# Schematics-IO.net
KiCad netlist of a schematic drawn in Altium Designer
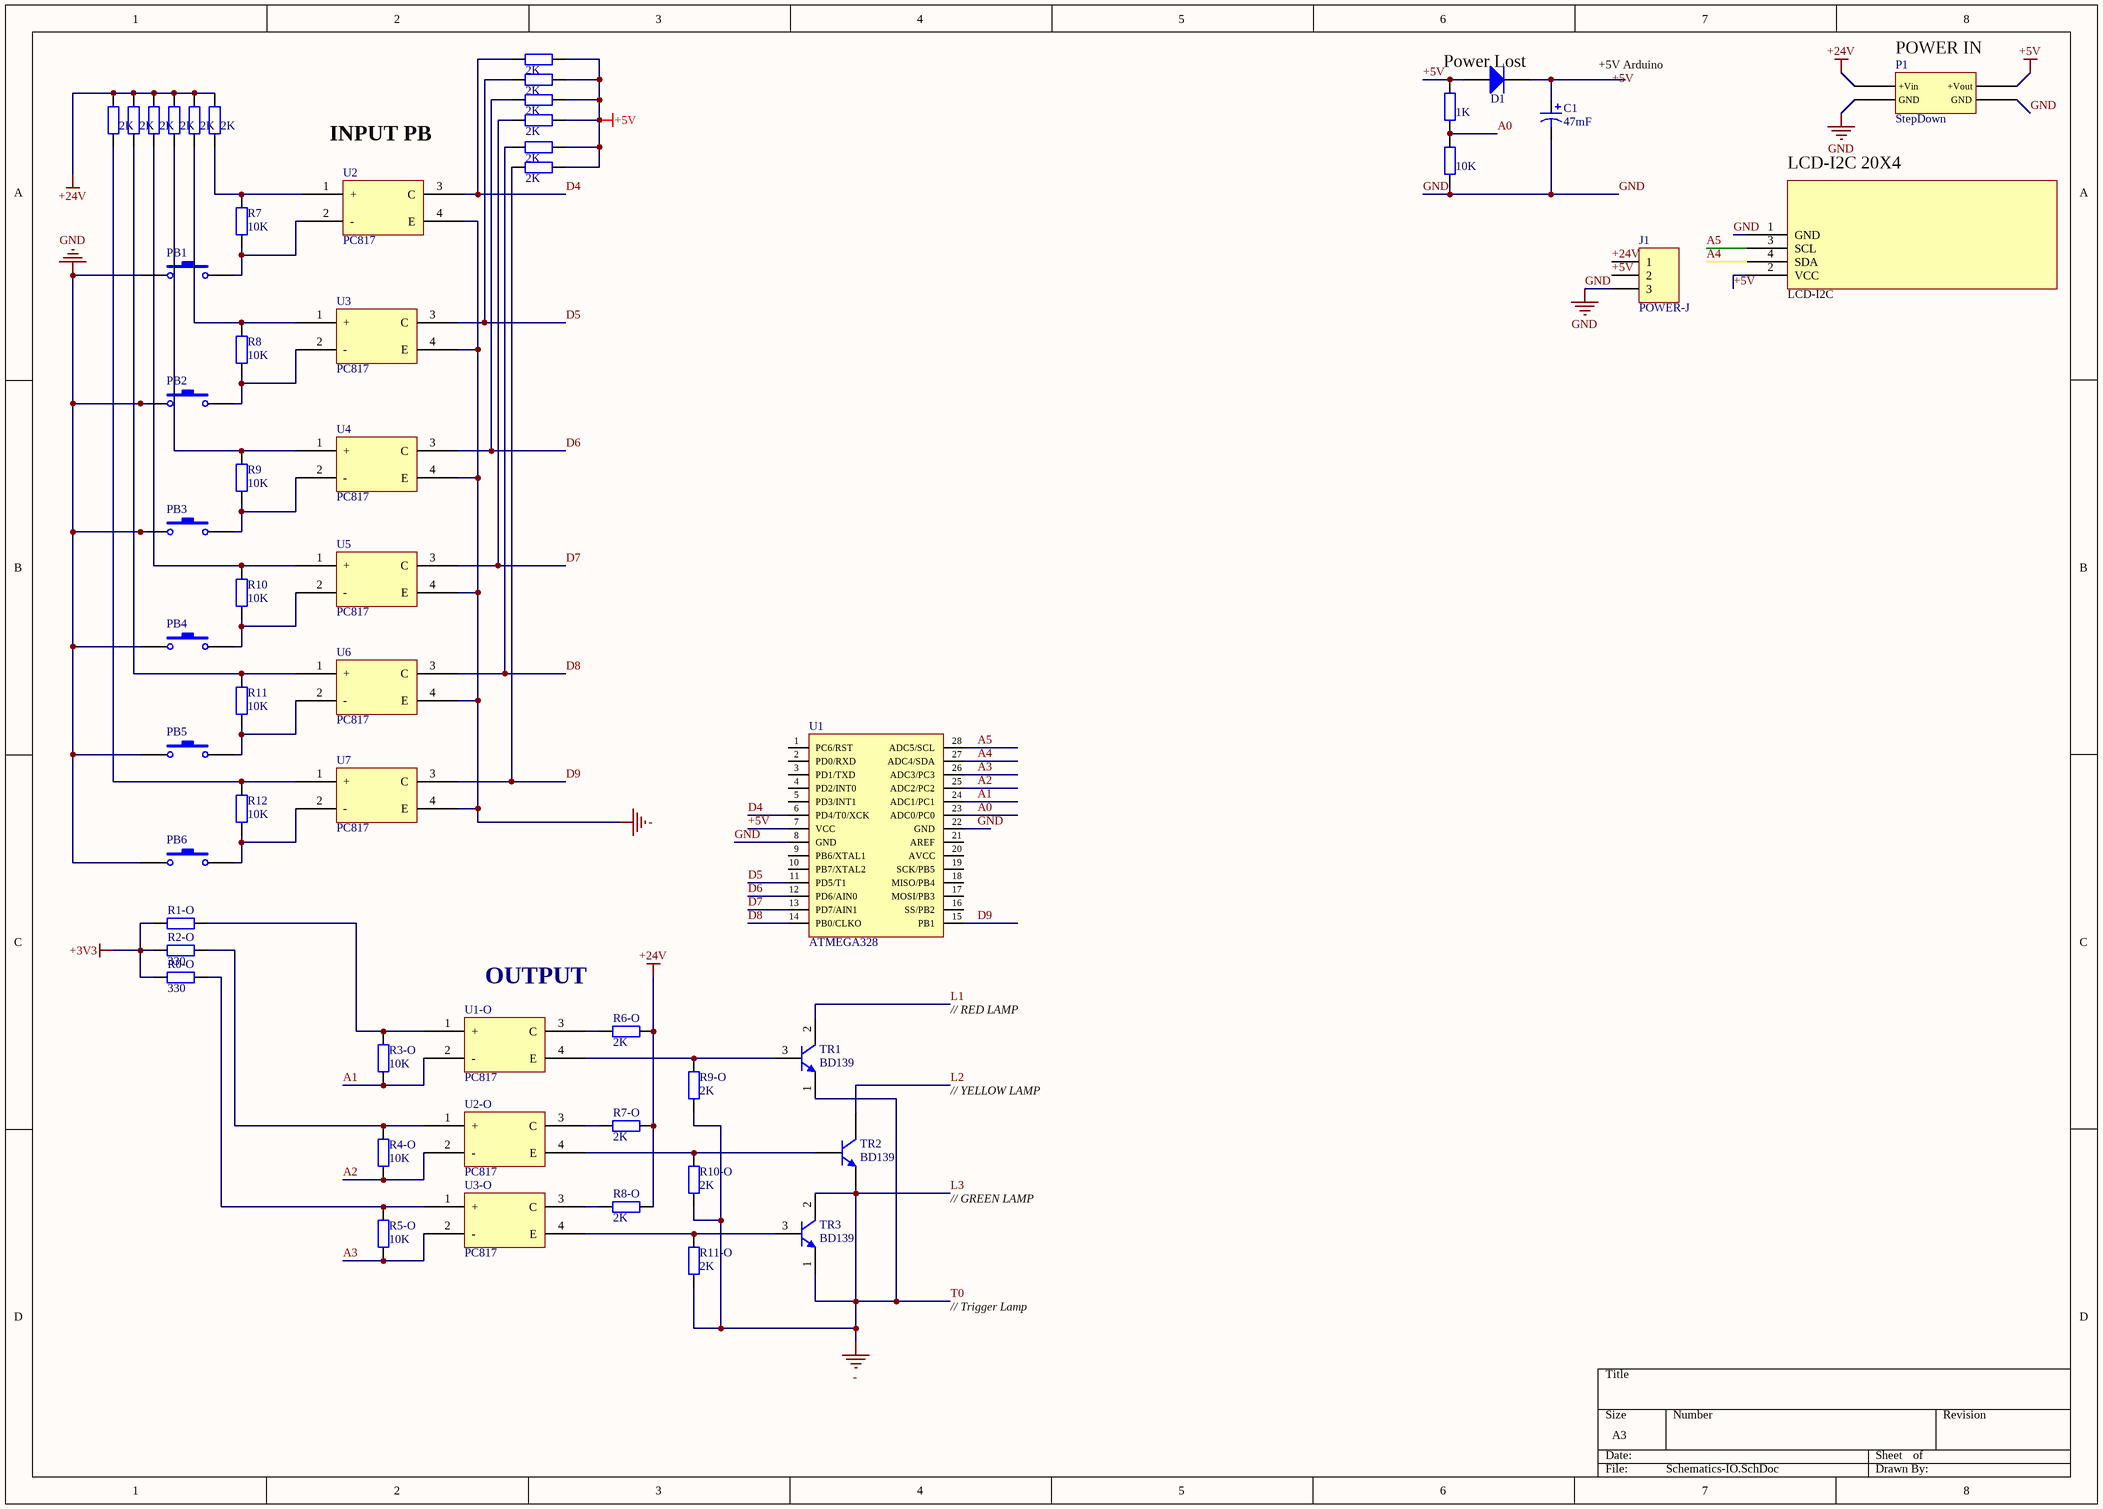
[diagram p0: Schematics-IO.SchDoc]

(export (version "E")
  (design (tool "Eeschema 10.0.6"))
  (components
    (comp (ref "C1")
      (value "47mF")
      (footprint "RB7.6-15")
      (description "Polarized Capacitor (Radial)")
      (fields (field (name "Comment") "p Pol1") (field (name "PUBLISHER") "Altium Limited"))
      (libsource (lib "Miscellaneous Devices") (part "Cap Pol1"))
    )
    (comp (ref "D1")
      (value "Diode")
      (footprint "SMC")
      (description "Default Diode")
      (fields (field (name "PUBLISHER") "Altium Limited"))
      (libsource (lib "Miscellaneous Devices") (part "Diode"))
    )
    (comp (ref "J1")
      (value "POWER-J")
      (footprint "HDR1X3")
      (description "Header, 3-Pin")
      (fields (field (name "PUBLISHER") "Altium Limited"))
      (libsource (lib "Miscellaneous Connectors") (part "Header 3"))
    )
    (comp (ref "P1") (value "StepDown") (footprint "MODULE4") (libsource (lib "LIBRARY_1") (part "StepDown")))
    (comp (ref "PB1")
      (value "NG+")
      (footprint "SPST-2")
      (description "Switch")
      (fields (field (name "PUBLISHER") "Altium Limited"))
      (libsource (lib "Miscellaneous Devices") (part "SW-PB"))
    )
    (comp (ref "PB2")
      (value "NG+")
      (footprint "SPST-2")
      (description "Switch")
      (fields (field (name "PUBLISHER") "Altium Limited"))
      (libsource (lib "Miscellaneous Devices") (part "SW-PB"))
    )
    (comp (ref "PB3")
      (value "NG+")
      (footprint "SPST-2")
      (description "Switch")
      (fields (field (name "PUBLISHER") "Altium Limited"))
      (libsource (lib "Miscellaneous Devices") (part "SW-PB"))
    )
    (comp (ref "PB4")
      (value "NG+")
      (footprint "SPST-2")
      (description "Switch")
      (fields (field (name "PUBLISHER") "Altium Limited"))
      (libsource (lib "Miscellaneous Devices") (part "SW-PB"))
    )
    (comp (ref "PB5")
      (value "NG+")
      (footprint "SPST-2")
      (description "Switch")
      (fields (field (name "PUBLISHER") "Altium Limited"))
      (libsource (lib "Miscellaneous Devices") (part "SW-PB"))
    )
    (comp (ref "PB6")
      (value "NG+")
      (footprint "SPST-2")
      (description "Switch")
      (fields (field (name "PUBLISHER") "Altium Limited"))
      (libsource (lib "Miscellaneous Devices") (part "SW-PB"))
    )
    (comp (ref "R0-O")
      (value "330")
      (footprint "AXIAL-0.4")
      (description "Resistor")
      (fields (field (name "Comment") "Res2") (field (name "PUBLISHER") "Altium Limited"))
      (libsource (lib "Miscellaneous Devices") (part "Res2"))
    )
    (comp (ref "R1")
      (value "2K")
      (footprint "AXIAL-0.4")
      (description "Resistor")
      (fields (field (name "Comment") "Res2") (field (name "PUBLISHER") "Altium Limited"))
      (libsource (lib "") (part "Res2_1"))
    )
    (comp (ref "R1-O")
      (value "Res2")
      (footprint "AXIAL-0.4")
      (description "Resistor")
      (fields (field (name "PUBLISHER") "Altium Limited"))
      (libsource (lib "Miscellaneous Devices") (part "Res2"))
    )
    (comp (ref "R2")
      (value "2K")
      (footprint "AXIAL-0.4")
      (description "Resistor")
      (fields (field (name "Comment") "Res2") (field (name "PUBLISHER") "Altium Limited"))
      (libsource (lib "") (part "Res2_1"))
    )
    (comp (ref "R2-O")
      (value "330")
      (footprint "AXIAL-0.4")
      (description "Resistor")
      (fields (field (name "Comment") "Res2") (field (name "PUBLISHER") "Altium Limited"))
      (libsource (lib "Miscellaneous Devices") (part "Res2"))
    )
    (comp (ref "R3")
      (value "2K")
      (footprint "AXIAL-0.4")
      (description "Resistor")
      (fields (field (name "Comment") "Res2") (field (name "PUBLISHER") "Altium Limited"))
      (libsource (lib "") (part "Res2_1"))
    )
    (comp (ref "R3-O")
      (value "10K")
      (footprint "AXIAL-0.4")
      (description "Resistor")
      (fields (field (name "Comment") "Res2") (field (name "PUBLISHER") "Altium Limited"))
      (libsource (lib "") (part "Res2_1"))
    )
    (comp (ref "R4")
      (value "2K")
      (footprint "AXIAL-0.4")
      (description "Resistor")
      (fields (field (name "Comment") "Res2") (field (name "PUBLISHER") "Altium Limited"))
      (libsource (lib "") (part "Res2_1"))
    )
    (comp (ref "R4-O")
      (value "10K")
      (footprint "AXIAL-0.4")
      (description "Resistor")
      (fields (field (name "Comment") "Res2") (field (name "PUBLISHER") "Altium Limited"))
      (libsource (lib "") (part "Res2_1"))
    )
    (comp (ref "R5")
      (value "2K")
      (footprint "AXIAL-0.4")
      (description "Resistor")
      (fields (field (name "Comment") "Res2") (field (name "PUBLISHER") "Altium Limited"))
      (libsource (lib "") (part "Res2_1"))
    )
    (comp (ref "R5-O")
      (value "10K")
      (footprint "AXIAL-0.4")
      (description "Resistor")
      (fields (field (name "Comment") "Res2") (field (name "PUBLISHER") "Altium Limited"))
      (libsource (lib "") (part "Res2_1"))
    )
    (comp (ref "R6")
      (value "2K")
      (footprint "AXIAL-0.4")
      (description "Resistor")
      (fields (field (name "Comment") "Res2") (field (name "PUBLISHER") "Altium Limited"))
      (libsource (lib "") (part "Res2_1"))
    )
    (comp (ref "R6-O")
      (value "2K")
      (footprint "AXIAL-0.4")
      (description "Resistor")
      (fields (field (name "Comment") "Res2") (field (name "PUBLISHER") "Altium Limited"))
      (libsource (lib "Miscellaneous Devices") (part "Res2"))
    )
    (comp (ref "R7")
      (value "10K")
      (footprint "AXIAL-0.4")
      (description "Resistor")
      (fields (field (name "Comment") "Res2") (field (name "PUBLISHER") "Altium Limited"))
      (libsource (lib "") (part "Res2_3"))
    )
    (comp (ref "R7-O")
      (value "2K")
      (footprint "AXIAL-0.4")
      (description "Resistor")
      (fields (field (name "Comment") "Res2") (field (name "PUBLISHER") "Altium Limited"))
      (libsource (lib "Miscellaneous Devices") (part "Res2"))
    )
    (comp (ref "R8")
      (value "10K")
      (footprint "AXIAL-0.4")
      (description "Resistor")
      (fields (field (name "Comment") "Res2") (field (name "PUBLISHER") "Altium Limited"))
      (libsource (lib "") (part "Res2_3"))
    )
    (comp (ref "R8-O")
      (value "2K")
      (footprint "AXIAL-0.4")
      (description "Resistor")
      (fields (field (name "Comment") "Res2") (field (name "PUBLISHER") "Altium Limited"))
      (libsource (lib "Miscellaneous Devices") (part "Res2"))
    )
    (comp (ref "R9")
      (value "10K")
      (footprint "AXIAL-0.4")
      (description "Resistor")
      (fields (field (name "Comment") "Res2") (field (name "PUBLISHER") "Altium Limited"))
      (libsource (lib "") (part "Res2_3"))
    )
    (comp (ref "R9-O")
      (value "2K")
      (footprint "AXIAL-0.4")
      (description "Resistor")
      (fields (field (name "Comment") "Res2") (field (name "PUBLISHER") "Altium Limited"))
      (libsource (lib "") (part "Res2_3"))
    )
    (comp (ref "R10")
      (value "10K")
      (footprint "AXIAL-0.4")
      (description "Resistor")
      (fields (field (name "Comment") "Res2") (field (name "PUBLISHER") "Altium Limited"))
      (libsource (lib "") (part "Res2_3"))
    )
    (comp (ref "R10-O")
      (value "2K")
      (footprint "AXIAL-0.4")
      (description "Resistor")
      (fields (field (name "Comment") "Res2") (field (name "PUBLISHER") "Altium Limited"))
      (libsource (lib "") (part "Res2_3"))
    )
    (comp (ref "R11")
      (value "10K")
      (footprint "AXIAL-0.4")
      (description "Resistor")
      (fields (field (name "Comment") "Res2") (field (name "PUBLISHER") "Altium Limited"))
      (libsource (lib "") (part "Res2_3"))
    )
    (comp (ref "R11-O")
      (value "2K")
      (footprint "AXIAL-0.4")
      (description "Resistor")
      (fields (field (name "Comment") "Res2") (field (name "PUBLISHER") "Altium Limited"))
      (libsource (lib "") (part "Res2_3"))
    )
    (comp (ref "R12")
      (value "10K")
      (footprint "AXIAL-0.4")
      (description "Resistor")
      (fields (field (name "Comment") "Res2") (field (name "PUBLISHER") "Altium Limited"))
      (libsource (lib "") (part "Res2_3"))
    )
    (comp (ref "R13")
      (value "2K")
      (footprint "AXIAL-0.4")
      (description "Resistor")
      (fields (field (name "Comment") "Res2") (field (name "PUBLISHER") "Altium Limited"))
      (libsource (lib "") (part "Res2_2"))
    )
    (comp (ref "R14")
      (value "2K")
      (footprint "AXIAL-0.4")
      (description "Resistor")
      (fields (field (name "Comment") "Res2") (field (name "PUBLISHER") "Altium Limited"))
      (libsource (lib "") (part "Res2_2"))
    )
    (comp (ref "R15")
      (value "2K")
      (footprint "AXIAL-0.4")
      (description "Resistor")
      (fields (field (name "Comment") "Res2") (field (name "PUBLISHER") "Altium Limited"))
      (libsource (lib "") (part "Res2_2"))
    )
    (comp (ref "R16")
      (value "2K")
      (footprint "AXIAL-0.4")
      (description "Resistor")
      (fields (field (name "Comment") "Res2") (field (name "PUBLISHER") "Altium Limited"))
      (libsource (lib "") (part "Res2_2"))
    )
    (comp (ref "R17")
      (value "2K")
      (footprint "AXIAL-0.4")
      (description "Resistor")
      (fields (field (name "Comment") "Res2") (field (name "PUBLISHER") "Altium Limited"))
      (libsource (lib "") (part "Res2_2"))
    )
    (comp (ref "R18")
      (value "2K")
      (footprint "AXIAL-0.4")
      (description "Resistor")
      (fields (field (name "Comment") "Res2") (field (name "PUBLISHER") "Altium Limited"))
      (libsource (lib "") (part "Res2_2"))
    )
    (comp (ref "R19")
      (value "1K")
      (footprint "AXIAL-0.4")
      (description "Resistor")
      (fields (field (name "Comment") "Res2") (field (name "PUBLISHER") "Altium Limited"))
      (libsource (lib "") (part "Res2_1"))
    )
    (comp (ref "R20")
      (value "10K")
      (footprint "AXIAL-0.4")
      (description "Resistor")
      (fields (field (name "Comment") "Res2") (field (name "PUBLISHER") "Altium Limited"))
      (libsource (lib "") (part "Res2_1"))
    )
    (comp (ref "TR1")
      (value "BD139")
      (footprint "BD139")
      (description "NPN General Purpose Amplifier")
      (fields (field (name "PUBLISHER") "Altium Limited"))
      (libsource (lib "Miscellaneous Devices") (part "2N3904"))
    )
    (comp (ref "TR2")
      (value "BD139")
      (footprint "BD139")
      (description "NPN General Purpose Amplifier")
      (fields (field (name "PUBLISHER") "Altium Limited"))
      (libsource (lib "") (part "2N3904_1"))
    )
    (comp (ref "TR3")
      (value "BD139")
      (footprint "BD139")
      (description "NPN General Purpose Amplifier")
      (fields (field (name "PUBLISHER") "Altium Limited"))
      (libsource (lib "Miscellaneous Devices") (part "2N3904"))
    )
    (comp (ref "U1") (value "ATMEGA328") (footprint "at328") (libsource (lib "LIBRARY_1") (part "ATMEGA328")))
    (comp (ref "U1-O") (value "PC817") (footprint "PC817") (libsource (lib "LIBRARY_1") (part "PC817")))
    (comp (ref "U2") (value "PC817") (footprint "PC817") (libsource (lib "LIBRARY_1") (part "PC817")))
    (comp (ref "U2-O") (value "PC817") (footprint "PC817") (libsource (lib "LIBRARY_1") (part "PC817")))
    (comp (ref "U3") (value "PC817") (footprint "PC817") (libsource (lib "LIBRARY_1") (part "PC817")))
    (comp (ref "U3-O") (value "PC817") (footprint "PC817") (libsource (lib "LIBRARY_1") (part "PC817")))
    (comp (ref "U4") (value "PC817") (footprint "PC817") (libsource (lib "LIBRARY_1") (part "PC817")))
    (comp (ref "U5") (value "PC817") (footprint "PC817") (libsource (lib "LIBRARY_1") (part "PC817")))
    (comp (ref "U6") (value "PC817") (footprint "PC817") (libsource (lib "LIBRARY_1") (part "PC817")))
    (comp (ref "U7") (value "PC817") (footprint "PC817") (libsource (lib "LIBRARY_1") (part "PC817")))
    (comp (ref "U99") (value "LCD-I2C") (footprint "MHDR1X4") (libsource (lib "LIBRARY_1") (part "I2C")))
  )
  (nets
    (net (code "1") (name "+3V3") (class "Default")
      (node (ref "R0-O") (pin "1") (pinfunction "1_1") (pintype "passive"))
      (node (ref "R1-O") (pin "1") (pinfunction "1_1") (pintype "passive"))
      (node (ref "R2-O") (pin "1") (pinfunction "1_1") (pintype "passive"))
    )
    (net (code "2") (name "+5V") (class "Default")
      (node (ref "D1") (pin "1") (pinfunction "A_1") (pintype "passive"))
      (node (ref "J1") (pin "2") (pinfunction "2_2") (pintype "passive"))
      (node (ref "P1") (pin "3") (pinfunction "+Vout_3") (pintype "passive"))
      (node (ref "R13") (pin "1") (pinfunction "1_1") (pintype "passive"))
      (node (ref "R14") (pin "1") (pinfunction "1_1") (pintype "passive"))
      (node (ref "R15") (pin "1") (pinfunction "1_1") (pintype "passive"))
      (node (ref "R16") (pin "1") (pinfunction "1_1") (pintype "passive"))
      (node (ref "R17") (pin "1") (pinfunction "1_1") (pintype "passive"))
      (node (ref "R18") (pin "1") (pinfunction "1_1") (pintype "passive"))
      (node (ref "R19") (pin "1") (pinfunction "1_1") (pintype "passive"))
      (node (ref "U1") (pin "7") (pinfunction "VCC_7") (pintype "passive"))
      (node (ref "U99") (pin "2") (pinfunction "VCC_2") (pintype "passive"))
    )
    (net (code "3") (name "+24V") (class "Default")
      (node (ref "J1") (pin "1") (pinfunction "1_1") (pintype "passive"))
      (node (ref "P1") (pin "1") (pinfunction "+Vin_1") (pintype "passive"))
      (node (ref "R1") (pin "1") (pinfunction "1_1") (pintype "passive"))
      (node (ref "R2") (pin "1") (pinfunction "1_1") (pintype "passive"))
      (node (ref "R3") (pin "1") (pinfunction "1_1") (pintype "passive"))
      (node (ref "R4") (pin "1") (pinfunction "1_1") (pintype "passive"))
      (node (ref "R5") (pin "1") (pinfunction "1_1") (pintype "passive"))
      (node (ref "R6") (pin "1") (pinfunction "1_1") (pintype "passive"))
      (node (ref "R6-O") (pin "2") (pinfunction "2_2") (pintype "passive"))
      (node (ref "R7-O") (pin "2") (pinfunction "2_2") (pintype "passive"))
      (node (ref "R8-O") (pin "2") (pinfunction "2_2") (pintype "passive"))
    )
    (net (code "4") (name "-") (class "Default")
      (node (ref "R10-O") (pin "1") (pinfunction "1_1") (pintype "passive"))
      (node (ref "R11-O") (pin "1") (pinfunction "1_1") (pintype "passive"))
      (node (ref "R9-O") (pin "1") (pinfunction "1_1") (pintype "passive"))
      (node (ref "TR1") (pin "1") (pinfunction "E_1") (pintype "passive"))
      (node (ref "TR2") (pin "1") (pinfunction "E_1") (pintype "passive"))
      (node (ref "TR3") (pin "1") (pinfunction "E_1") (pintype "passive"))
      (node (ref "TR3") (pin "2") (pinfunction "C_2") (pintype "passive"))
      (node (ref "U2") (pin "4") (pinfunction "E_4") (pintype "passive"))
      (node (ref "U3") (pin "4") (pinfunction "E_4") (pintype "passive"))
      (node (ref "U4") (pin "4") (pinfunction "E_4") (pintype "passive"))
      (node (ref "U5") (pin "4") (pinfunction "E_4") (pintype "passive"))
      (node (ref "U6") (pin "4") (pinfunction "E_4") (pintype "passive"))
      (node (ref "U7") (pin "4") (pinfunction "E_4") (pintype "passive"))
    )
    (net (code "5") (name "/A0") (class "Default")
      (node (ref "R19") (pin "2") (pinfunction "2_2") (pintype "passive"))
      (node (ref "R20") (pin "1") (pinfunction "1_1") (pintype "passive"))
      (node (ref "U1") (pin "23") (pinfunction "ADC0/PC0_23") (pintype "passive"))
    )
    (net (code "6") (name "/A1") (class "Default")
      (node (ref "R3-O") (pin "2") (pinfunction "2_2") (pintype "passive"))
      (node (ref "U1") (pin "24") (pinfunction "ADC1/PC1_24") (pintype "passive"))
      (node (ref "U1-O") (pin "2") (pinfunction "-_2") (pintype "passive"))
    )
    (net (code "7") (name "/A2") (class "Default")
      (node (ref "R4-O") (pin "2") (pinfunction "2_2") (pintype "passive"))
      (node (ref "U1") (pin "25") (pinfunction "ADC2/PC2_25") (pintype "passive"))
      (node (ref "U2-O") (pin "2") (pinfunction "-_2") (pintype "passive"))
    )
    (net (code "8") (name "/A3") (class "Default")
      (node (ref "R5-O") (pin "2") (pinfunction "2_2") (pintype "passive"))
      (node (ref "U1") (pin "26") (pinfunction "ADC3/PC3_26") (pintype "passive"))
      (node (ref "U3-O") (pin "2") (pinfunction "-_2") (pintype "passive"))
    )
    (net (code "9") (name "/A4") (class "Default")
      (node (ref "U1") (pin "27") (pinfunction "ADC4/SDA_27") (pintype "passive"))
      (node (ref "U99") (pin "4") (pinfunction "SDA_4") (pintype "passive"))
    )
    (net (code "10") (name "/A5") (class "Default")
      (node (ref "U1") (pin "28") (pinfunction "ADC5/SCL_28") (pintype "passive"))
      (node (ref "U99") (pin "3") (pinfunction "SCL_3") (pintype "passive"))
    )
    (net (code "11") (name "/D4") (class "Default")
      (node (ref "R13") (pin "2") (pinfunction "2_2") (pintype "passive"))
      (node (ref "U1") (pin "6") (pinfunction "PD4/T0/XCK_6") (pintype "passive"))
      (node (ref "U2") (pin "3") (pinfunction "C_3") (pintype "passive"))
    )
    (net (code "12") (name "/D5") (class "Default")
      (node (ref "R14") (pin "2") (pinfunction "2_2") (pintype "passive"))
      (node (ref "U1") (pin "11") (pinfunction "PD5/T1_11") (pintype "passive"))
      (node (ref "U3") (pin "3") (pinfunction "C_3") (pintype "passive"))
    )
    (net (code "13") (name "/D6") (class "Default")
      (node (ref "R15") (pin "2") (pinfunction "2_2") (pintype "passive"))
      (node (ref "U1") (pin "12") (pinfunction "PD6/AIN0_12") (pintype "passive"))
      (node (ref "U4") (pin "3") (pinfunction "C_3") (pintype "passive"))
    )
    (net (code "14") (name "/D7") (class "Default")
      (node (ref "R16") (pin "2") (pinfunction "2_2") (pintype "passive"))
      (node (ref "U1") (pin "13") (pinfunction "PD7/AIN1_13") (pintype "passive"))
      (node (ref "U5") (pin "3") (pinfunction "C_3") (pintype "passive"))
    )
    (net (code "15") (name "/D8") (class "Default")
      (node (ref "R17") (pin "2") (pinfunction "2_2") (pintype "passive"))
      (node (ref "U1") (pin "14") (pinfunction "PB0/CLKO_14") (pintype "passive"))
      (node (ref "U6") (pin "3") (pinfunction "C_3") (pintype "passive"))
    )
    (net (code "16") (name "/D9") (class "Default")
      (node (ref "R18") (pin "2") (pinfunction "2_2") (pintype "passive"))
      (node (ref "U1") (pin "15") (pinfunction "PB1_15") (pintype "passive"))
      (node (ref "U7") (pin "3") (pinfunction "C_3") (pintype "passive"))
    )
    (net (code "17") (name "/L1") (class "Default")
      (node (ref "TR1") (pin "2") (pinfunction "C_2") (pintype "passive"))
    )
    (net (code "18") (name "/L2") (class "Default")
      (node (ref "TR2") (pin "2") (pinfunction "C_2") (pintype "passive"))
    )
    (net (code "19") (name "GND") (class "Default")
      (node (ref "C1") (pin "2") (pinfunction "2_2") (pintype "passive"))
      (node (ref "J1") (pin "3") (pinfunction "3_3") (pintype "passive"))
      (node (ref "P1") (pin "2") (pinfunction "GND_2") (pintype "passive"))
      (node (ref "P1") (pin "4") (pinfunction "GND_4") (pintype "passive"))
      (node (ref "PB1") (pin "1") (pinfunction "1_1") (pintype "passive"))
      (node (ref "PB2") (pin "1") (pinfunction "1_1") (pintype "passive"))
      (node (ref "PB3") (pin "1") (pinfunction "1_1") (pintype "passive"))
      (node (ref "PB4") (pin "1") (pinfunction "1_1") (pintype "passive"))
      (node (ref "PB5") (pin "1") (pinfunction "1_1") (pintype "passive"))
      (node (ref "PB6") (pin "1") (pinfunction "1_1") (pintype "passive"))
      (node (ref "R20") (pin "2") (pinfunction "2_2") (pintype "passive"))
      (node (ref "U1") (pin "22") (pinfunction "GND_22") (pintype "passive"))
      (node (ref "U1") (pin "8") (pinfunction "GND_8") (pintype "passive"))
      (node (ref "U99") (pin "1") (pinfunction "GND_1") (pintype "passive"))
    )
    (net (code "20") (name "Net-(D1-K)") (class "Default")
      (node (ref "C1") (pin "1") (pinfunction "1_1") (pintype "passive"))
      (node (ref "D1") (pin "2") (pinfunction "K_2") (pintype "passive"))
    )
    (net (code "21") (name "Net-(TR1-B)") (class "Default")
      (node (ref "R9-O") (pin "2") (pinfunction "2_2") (pintype "passive"))
      (node (ref "TR1") (pin "3") (pinfunction "B_3") (pintype "passive"))
      (node (ref "U1-O") (pin "4") (pinfunction "E_4") (pintype "passive"))
    )
    (net (code "22") (name "Net-(TR2-B)") (class "Default")
      (node (ref "R10-O") (pin "2") (pinfunction "2_2") (pintype "passive"))
      (node (ref "TR2") (pin "3") (pinfunction "B_3") (pintype "passive"))
      (node (ref "U2-O") (pin "4") (pinfunction "E_4") (pintype "passive"))
    )
    (net (code "23") (name "Net-(TR3-B)") (class "Default")
      (node (ref "R11-O") (pin "2") (pinfunction "2_2") (pintype "passive"))
      (node (ref "TR3") (pin "3") (pinfunction "B_3") (pintype "passive"))
      (node (ref "U3-O") (pin "4") (pinfunction "E_4") (pintype "passive"))
    )
    (net (code "24") (name "Net-(U1-O-+)") (class "Default")
      (node (ref "R1-O") (pin "2") (pinfunction "2_2") (pintype "passive"))
      (node (ref "R3-O") (pin "1") (pinfunction "1_1") (pintype "passive"))
      (node (ref "U1-O") (pin "1") (pinfunction "+_1") (pintype "passive"))
    )
    (net (code "25") (name "Net-(U1-O-C)") (class "Default")
      (node (ref "R6-O") (pin "1") (pinfunction "1_1") (pintype "passive"))
      (node (ref "U1-O") (pin "3") (pinfunction "C_3") (pintype "passive"))
    )
    (net (code "26") (name "Net-(U2-+)") (class "Default")
      (node (ref "R6") (pin "2") (pinfunction "2_2") (pintype "passive"))
      (node (ref "R7") (pin "2") (pinfunction "2_2") (pintype "passive"))
      (node (ref "U2") (pin "1") (pinfunction "+_1") (pintype "passive"))
    )
    (net (code "27") (name "Net-(U2--)") (class "Default")
      (node (ref "PB1") (pin "2") (pinfunction "2_2") (pintype "passive"))
      (node (ref "R7") (pin "1") (pinfunction "1_1") (pintype "passive"))
      (node (ref "U2") (pin "2") (pinfunction "-_2") (pintype "passive"))
    )
    (net (code "28") (name "Net-(U2-O-+)") (class "Default")
      (node (ref "R2-O") (pin "2") (pinfunction "2_2") (pintype "passive"))
      (node (ref "R4-O") (pin "1") (pinfunction "1_1") (pintype "passive"))
      (node (ref "U2-O") (pin "1") (pinfunction "+_1") (pintype "passive"))
    )
    (net (code "29") (name "Net-(U2-O-C)") (class "Default")
      (node (ref "R7-O") (pin "1") (pinfunction "1_1") (pintype "passive"))
      (node (ref "U2-O") (pin "3") (pinfunction "C_3") (pintype "passive"))
    )
    (net (code "30") (name "Net-(U3-+)") (class "Default")
      (node (ref "R5") (pin "2") (pinfunction "2_2") (pintype "passive"))
      (node (ref "R8") (pin "2") (pinfunction "2_2") (pintype "passive"))
      (node (ref "U3") (pin "1") (pinfunction "+_1") (pintype "passive"))
    )
    (net (code "31") (name "Net-(U3--)") (class "Default")
      (node (ref "PB2") (pin "2") (pinfunction "2_2") (pintype "passive"))
      (node (ref "R8") (pin "1") (pinfunction "1_1") (pintype "passive"))
      (node (ref "U3") (pin "2") (pinfunction "-_2") (pintype "passive"))
    )
    (net (code "32") (name "Net-(U3-O-+)") (class "Default")
      (node (ref "R0-O") (pin "2") (pinfunction "2_2") (pintype "passive"))
      (node (ref "R5-O") (pin "1") (pinfunction "1_1") (pintype "passive"))
      (node (ref "U3-O") (pin "1") (pinfunction "+_1") (pintype "passive"))
    )
    (net (code "33") (name "Net-(U3-O-C)") (class "Default")
      (node (ref "R8-O") (pin "1") (pinfunction "1_1") (pintype "passive"))
      (node (ref "U3-O") (pin "3") (pinfunction "C_3") (pintype "passive"))
    )
    (net (code "34") (name "Net-(U4-+)") (class "Default")
      (node (ref "R4") (pin "2") (pinfunction "2_2") (pintype "passive"))
      (node (ref "R9") (pin "2") (pinfunction "2_2") (pintype "passive"))
      (node (ref "U4") (pin "1") (pinfunction "+_1") (pintype "passive"))
    )
    (net (code "35") (name "Net-(U4--)") (class "Default")
      (node (ref "PB3") (pin "2") (pinfunction "2_2") (pintype "passive"))
      (node (ref "R9") (pin "1") (pinfunction "1_1") (pintype "passive"))
      (node (ref "U4") (pin "2") (pinfunction "-_2") (pintype "passive"))
    )
    (net (code "36") (name "Net-(U5-+)") (class "Default")
      (node (ref "R10") (pin "2") (pinfunction "2_2") (pintype "passive"))
      (node (ref "R3") (pin "2") (pinfunction "2_2") (pintype "passive"))
      (node (ref "U5") (pin "1") (pinfunction "+_1") (pintype "passive"))
    )
    (net (code "37") (name "Net-(U5--)") (class "Default")
      (node (ref "PB4") (pin "2") (pinfunction "2_2") (pintype "passive"))
      (node (ref "R10") (pin "1") (pinfunction "1_1") (pintype "passive"))
      (node (ref "U5") (pin "2") (pinfunction "-_2") (pintype "passive"))
    )
    (net (code "38") (name "Net-(U6-+)") (class "Default")
      (node (ref "R11") (pin "2") (pinfunction "2_2") (pintype "passive"))
      (node (ref "R2") (pin "2") (pinfunction "2_2") (pintype "passive"))
      (node (ref "U6") (pin "1") (pinfunction "+_1") (pintype "passive"))
    )
    (net (code "39") (name "Net-(U6--)") (class "Default")
      (node (ref "PB5") (pin "2") (pinfunction "2_2") (pintype "passive"))
      (node (ref "R11") (pin "1") (pinfunction "1_1") (pintype "passive"))
      (node (ref "U6") (pin "2") (pinfunction "-_2") (pintype "passive"))
    )
    (net (code "40") (name "Net-(U7-+)") (class "Default")
      (node (ref "R1") (pin "2") (pinfunction "2_2") (pintype "passive"))
      (node (ref "R12") (pin "2") (pinfunction "2_2") (pintype "passive"))
      (node (ref "U7") (pin "1") (pinfunction "+_1") (pintype "passive"))
    )
    (net (code "41") (name "Net-(U7--)") (class "Default")
      (node (ref "PB6") (pin "2") (pinfunction "2_2") (pintype "passive"))
      (node (ref "R12") (pin "1") (pinfunction "1_1") (pintype "passive"))
      (node (ref "U7") (pin "2") (pinfunction "-_2") (pintype "passive"))
    )
    (net (code "42") (name "unconnected-(U1-AREF-Pad21)") (class "Default")
      (node (ref "U1") (pin "21") (pinfunction "AREF_21") (pintype "passive"))
    )
    (net (code "43") (name "unconnected-(U1-AVCC-Pad20)") (class "Default")
      (node (ref "U1") (pin "20") (pinfunction "AVCC_20") (pintype "passive"))
    )
    (net (code "44") (name "unconnected-(U1-MISO{slash}PB4-Pad18)") (class "Default")
      (node (ref "U1") (pin "18") (pinfunction "MISO/PB4_18") (pintype "passive"))
    )
    (net (code "45") (name "unconnected-(U1-MOSI{slash}PB3-Pad17)") (class "Default")
      (node (ref "U1") (pin "17") (pinfunction "MOSI/PB3_17") (pintype "passive"))
    )
    (net (code "46") (name "unconnected-(U1-PB6{slash}XTAL1-Pad9)") (class "Default")
      (node (ref "U1") (pin "9") (pinfunction "PB6/XTAL1_9") (pintype "passive"))
    )
    (net (code "47") (name "unconnected-(U1-PB7{slash}XTAL2-Pad10)") (class "Default")
      (node (ref "U1") (pin "10") (pinfunction "PB7/XTAL2_10") (pintype "passive"))
    )
    (net (code "48") (name "unconnected-(U1-PC6{slash}RST-Pad1)") (class "Default")
      (node (ref "U1") (pin "1") (pinfunction "PC6/RST_1") (pintype "passive"))
    )
    (net (code "49") (name "unconnected-(U1-PD0{slash}RXD-Pad2)") (class "Default")
      (node (ref "U1") (pin "2") (pinfunction "PD0/RXD_2") (pintype "passive"))
    )
    (net (code "50") (name "unconnected-(U1-PD1{slash}TXD-Pad3)") (class "Default")
      (node (ref "U1") (pin "3") (pinfunction "PD1/TXD_3") (pintype "passive"))
    )
    (net (code "51") (name "unconnected-(U1-PD2{slash}INT0-Pad4)") (class "Default")
      (node (ref "U1") (pin "4") (pinfunction "PD2/INT0_4") (pintype "passive"))
    )
    (net (code "52") (name "unconnected-(U1-PD3{slash}INT1-Pad5)") (class "Default")
      (node (ref "U1") (pin "5") (pinfunction "PD3/INT1_5") (pintype "passive"))
    )
    (net (code "53") (name "unconnected-(U1-SCK{slash}PB5-Pad19)") (class "Default")
      (node (ref "U1") (pin "19") (pinfunction "SCK/PB5_19") (pintype "passive"))
    )
    (net (code "54") (name "unconnected-(U1-SS{slash}PB2-Pad16)") (class "Default")
      (node (ref "U1") (pin "16") (pinfunction "SS/PB2_16") (pintype "passive"))
    )
    (net (code "55") (name "unconnected-(U99-15-Pad2)") (class "Default")
      (node (ref "U99") (pin "2") (pinfunction "15_2") (pintype "passive"))
    )
    (net (code "56") (name "unconnected-(U99-16-Pad1)") (class "Default")
      (node (ref "U99") (pin "1") (pinfunction "16_1") (pintype "passive"))
    )
    (net (code "57") (name "unconnected-(U99-Pad1)") (class "Default")
      (node (ref "U99") (pin "1") (pinfunction "1_1") (pintype "passive"))
    )
    (net (code "58") (name "unconnected-(U99-Pad2)") (class "Default")
      (node (ref "U99") (pin "2") (pinfunction "2_2") (pintype "passive"))
    )
    (net (code "59") (name "unconnected-(U99-Pad3)") (class "Default")
      (node (ref "U99") (pin "3") (pinfunction "3_3") (pintype "passive"))
    )
    (net (code "60") (name "unconnected-(U99-Pad4)") (class "Default")
      (node (ref "U99") (pin "4") (pinfunction "4_4") (pintype "passive"))
    )
    (net (code "61") (name "unconnected-(U99-Pad5)") (class "Default")
      (node (ref "U99") (pin "5") (pinfunction "5_5") (pintype "passive"))
    )
    (net (code "62") (name "unconnected-(U99-Pad6)") (class "Default")
      (node (ref "U99") (pin "6") (pinfunction "6_6") (pintype "passive"))
    )
    (net (code "63") (name "unconnected-(U99-Pad7)") (class "Default")
      (node (ref "U99") (pin "7") (pinfunction "7_7") (pintype "passive"))
    )
    (net (code "64") (name "unconnected-(U99-Pad8)") (class "Default")
      (node (ref "U99") (pin "8") (pinfunction "8_8") (pintype "passive"))
    )
    (net (code "65") (name "unconnected-(U99-Pad9)") (class "Default")
      (node (ref "U99") (pin "9") (pinfunction "9_9") (pintype "passive"))
    )
    (net (code "66") (name "unconnected-(U99-Pad10)") (class "Default")
      (node (ref "U99") (pin "10") (pinfunction "10_10") (pintype "passive"))
    )
    (net (code "67") (name "unconnected-(U99-Pad11)") (class "Default")
      (node (ref "U99") (pin "11") (pinfunction "11_11") (pintype "passive"))
    )
    (net (code "68") (name "unconnected-(U99-Pad12)") (class "Default")
      (node (ref "U99") (pin "12") (pinfunction "12_12") (pintype "passive"))
    )
    (net (code "69") (name "unconnected-(U99-Pad13)") (class "Default")
      (node (ref "U99") (pin "13") (pinfunction "13_13") (pintype "passive"))
    )
    (net (code "70") (name "unconnected-(U99-Pad14)") (class "Default")
      (node (ref "U99") (pin "14") (pinfunction "14_14") (pintype "passive"))
    )
  )
)
